# current-limiter.net
KiCad netlist of a schematic drawn in Altium Designer
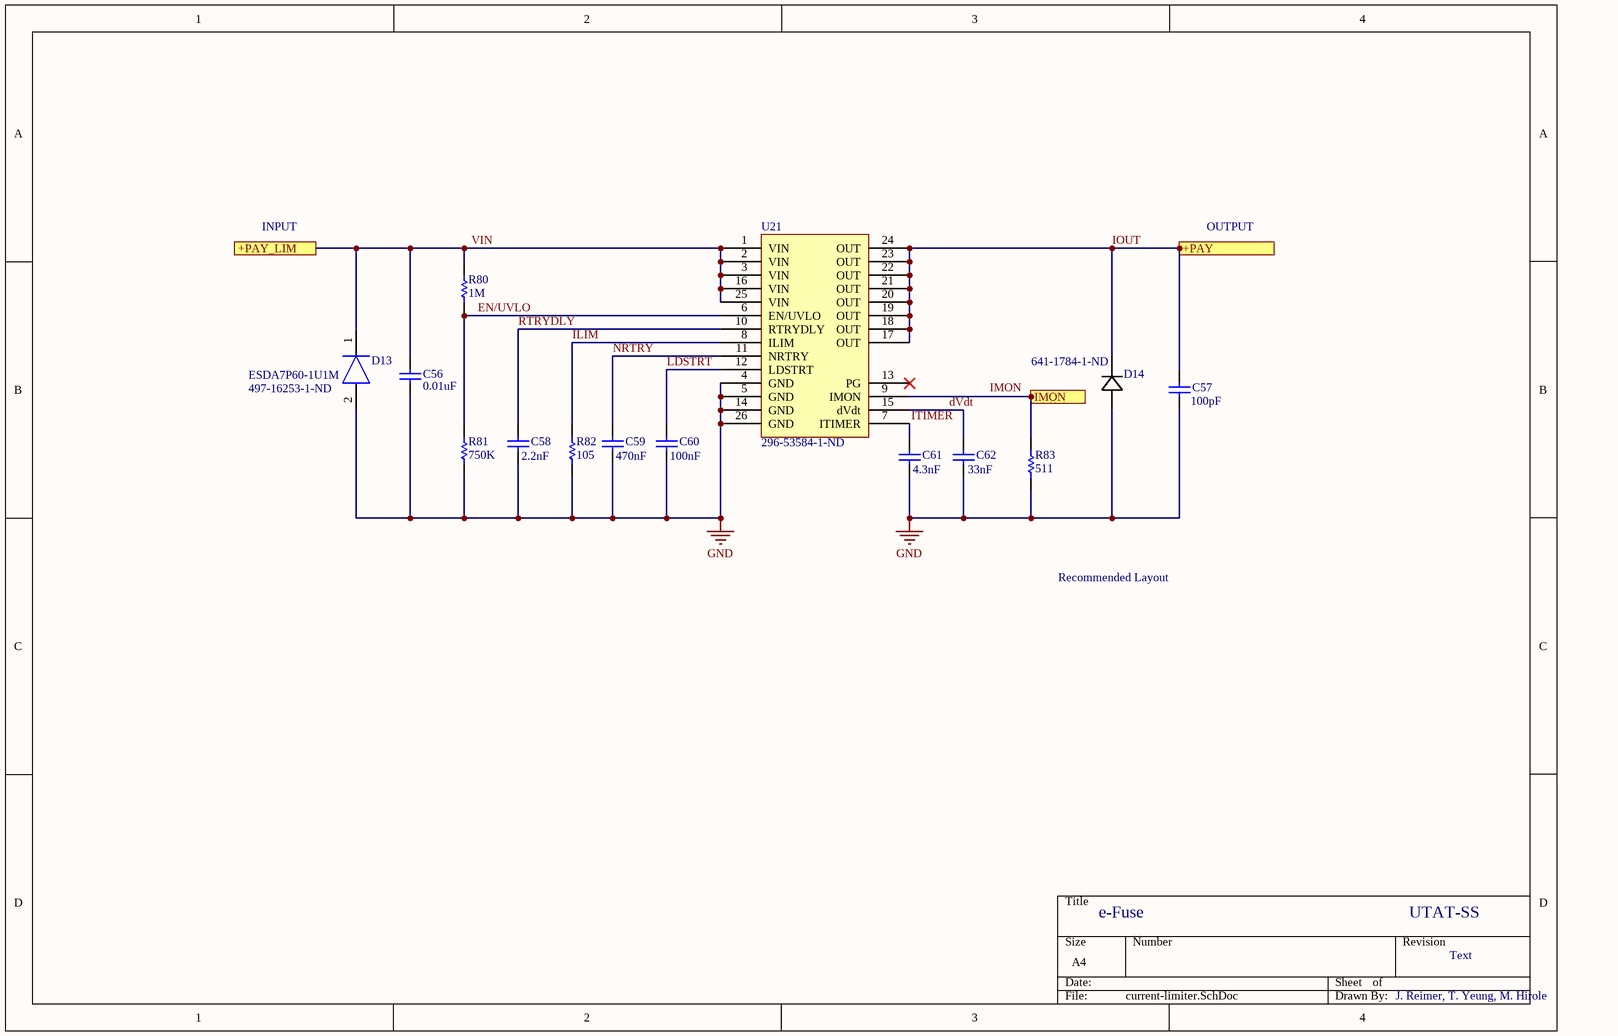
[diagram p0: current-limiter.SchDoc]

(export (version "E")
  (design (tool "Eeschema 10.0.6"))
  (components
    (comp (ref "C56")
      (value "0.01uF")
      (footprint "CAP0603R")
      (description "0603 capacitor")
      (fields (field (name "Comment") "0603"))
      (libsource (lib "heron-general") (part "CAP0603"))
    )
    (comp (ref "C57")
      (value "100pF")
      (footprint "CAP0603R")
      (description "0603 capacitor")
      (fields (field (name "Comment") "0603"))
      (libsource (lib "heron-general") (part "CAP0603"))
    )
    (comp (ref "C58")
      (value "2.2nF")
      (footprint "CAP0402R")
      (description "0402 capacitor")
      (fields (field (name "Comment") "0402"))
      (libsource (lib "heron-general") (part "CAP0402"))
    )
    (comp (ref "C59")
      (value "470nF")
      (footprint "CAP0402R")
      (description "0402 capacitor")
      (fields (field (name "Comment") "0402"))
      (libsource (lib "heron-general") (part "CAP0402"))
    )
    (comp (ref "C60")
      (value "100nF")
      (footprint "CAP0402R")
      (description "0402 capacitor")
      (fields (field (name "Comment") "0402"))
      (libsource (lib "heron-general") (part "CAP0402"))
    )
    (comp (ref "C61")
      (value "4.3nF")
      (footprint "CAP0402R")
      (description "0402 capacitor")
      (fields (field (name "Comment") "0402"))
      (libsource (lib "heron-general") (part "CAP0402"))
    )
    (comp (ref "C62")
      (value "33nF")
      (footprint "CAP0402R")
      (description "0402 capacitor")
      (fields (field (name "Comment") "0402"))
      (libsource (lib "heron-general") (part "CAP0402"))
    )
    (comp (ref "D13")
      (value "ESDA7P60-1U1M")
      (footprint "ESDA7P601U1M")
      (description "Diode")
      (fields
        (field (name "MOUSER PART NUMBER") "511-ESDA7P60-1U1M")
        (field (name "RS PART NUMBER") "1106381P")
        (field (name "SUPPLIER PART NUMBER 1") "497-16253-1-ND")
      )
      (libsource (lib "ESDA7P60-1U1M") (part "ESDA7P60-1U1M"))
    )
    (comp (ref "D14")
      (value "Part Number: 1SS389")
      (footprint "ESC")
      (description "No Description Available")
      (fields
        (field (name "MANUFACTURER_PART_NUMBER") "1SS389")
        (field (name "MANUFACTURER") "Comchip")
        (field (name "SUPPLIER PART NUMBER 1") "641-1784-1-ND")
        (field (name "COPYRIGHT") "Copyright (C) 2016 Accelerated Designs. All rights reserved")
      )
      (libsource (lib "1SS389") (part "1SS389"))
    )
    (comp (ref "R80")
      (value "1M")
      (footprint "RES0402R")
      (description "0402 resistor")
      (fields (field (name "Comment") "0402"))
      (libsource (lib "heron-general") (part "RES0402"))
    )
    (comp (ref "R81")
      (value "750K")
      (footprint "RES0402R")
      (description "0402 resistor")
      (fields (field (name "Comment") "0402"))
      (libsource (lib "heron-general") (part "RES0402"))
    )
    (comp (ref "R82")
      (value "105")
      (footprint "RES0402R")
      (description "0402 resistor")
      (fields (field (name "Comment") "0402"))
      (libsource (lib "heron-general") (part "RES0402"))
    )
    (comp (ref "R83")
      (value "511")
      (footprint "RES0402R")
      (description "0402 resistor")
      (fields (field (name "Comment") "0402"))
      (libsource (lib "heron-general") (part "RES0402"))
    )
    (comp (ref "U21")
      (value "eFuse")
      (footprint "RGE0024M")
      (description "2.7 - 24 V input supply, 15 A max load current")
      (fields
        (field (name "MANUFACTURER") "Texas Instruments")
        (field (name "MANUFACTURER PART NUMBER") "TPS259822LNRGER")
        (field (name "SUPPLIER PART NUMBER 1") "296-53584-1-ND")
      )
      (libsource (lib "heron-general") (part "TPS25982"))
    )
  )
  (nets
    (net (code "1") (name "/EN{slash}UVLO") (class "Default")
      (node (ref "R80") (pin "1") (pinfunction "1_1") (pintype "passive"))
      (node (ref "R81") (pin "2") (pinfunction "2_2") (pintype "passive"))
      (node (ref "U21") (pin "6") (pinfunction "EN/UVLO_6") (pintype "passive"))
    )
    (net (code "2") (name "/ILIM") (class "Default")
      (node (ref "R82") (pin "2") (pinfunction "2_2") (pintype "passive"))
      (node (ref "U21") (pin "8") (pinfunction "ILIM_8") (pintype "passive"))
    )
    (net (code "3") (name "/IMON") (class "Default")
      (node (ref "R83") (pin "2") (pinfunction "2_2") (pintype "passive"))
      (node (ref "U21") (pin "9") (pinfunction "IMON_9") (pintype "passive"))
    )
    (net (code "4") (name "/IOUT") (class "Default")
      (node (ref "C57") (pin "2") (pinfunction "2_2") (pintype "passive"))
      (node (ref "D14") (pin "1") (pinfunction "CATHODE_1") (pintype "passive"))
      (node (ref "U21") (pin "17") (pinfunction "OUT_17") (pintype "power_in"))
      (node (ref "U21") (pin "18") (pinfunction "OUT_18") (pintype "power_in"))
      (node (ref "U21") (pin "19") (pinfunction "OUT_19") (pintype "power_in"))
      (node (ref "U21") (pin "20") (pinfunction "OUT_20") (pintype "power_in"))
      (node (ref "U21") (pin "21") (pinfunction "OUT_21") (pintype "power_in"))
      (node (ref "U21") (pin "22") (pinfunction "OUT_22") (pintype "power_in"))
      (node (ref "U21") (pin "23") (pinfunction "OUT_23") (pintype "power_in"))
      (node (ref "U21") (pin "24") (pinfunction "OUT_24") (pintype "power_in"))
    )
    (net (code "6") (name "/LDSTRT") (class "Default")
      (node (ref "C60") (pin "2") (pinfunction "2_2") (pintype "passive"))
      (node (ref "U21") (pin "12") (pinfunction "LDSTRT_12") (pintype "passive"))
    )
    (net (code "7") (name "/NRTRY") (class "Default")
      (node (ref "C59") (pin "2") (pinfunction "2_2") (pintype "passive"))
      (node (ref "U21") (pin "11") (pinfunction "NRTRY_11") (pintype "passive"))
    )
    (net (code "8") (name "/RTRYDLY") (class "Default")
      (node (ref "C58") (pin "2") (pinfunction "2_2") (pintype "passive"))
      (node (ref "U21") (pin "10") (pinfunction "RTRYDLY_10") (pintype "passive"))
    )
    (net (code "9") (name "/VIN") (class "Default")
      (node (ref "C56") (pin "2") (pinfunction "2_2") (pintype "passive"))
      (node (ref "D13") (pin "1") (pinfunction "K_1") (pintype "passive"))
      (node (ref "R80") (pin "2") (pinfunction "2_2") (pintype "passive"))
      (node (ref "U21") (pin "1") (pinfunction "VIN_1") (pintype "power_in"))
      (node (ref "U21") (pin "16") (pinfunction "VIN_16") (pintype "power_in"))
      (node (ref "U21") (pin "2") (pinfunction "VIN_2") (pintype "power_in"))
      (node (ref "U21") (pin "25") (pinfunction "VIN_25") (pintype "power_in"))
      (node (ref "U21") (pin "3") (pinfunction "VIN_3") (pintype "power_in"))
    )
    (net (code "10") (name "/dVdt") (class "Default")
      (node (ref "C62") (pin "2") (pinfunction "2_2") (pintype "passive"))
      (node (ref "U21") (pin "15") (pinfunction "dVdt_15") (pintype "passive"))
    )
    (net (code "11") (name "GND") (class "Default")
      (node (ref "C56") (pin "1") (pinfunction "1_1") (pintype "passive"))
      (node (ref "C57") (pin "1") (pinfunction "1_1") (pintype "passive"))
      (node (ref "C58") (pin "1") (pinfunction "1_1") (pintype "passive"))
      (node (ref "C59") (pin "1") (pinfunction "1_1") (pintype "passive"))
      (node (ref "C60") (pin "1") (pinfunction "1_1") (pintype "passive"))
      (node (ref "C61") (pin "1") (pinfunction "1_1") (pintype "passive"))
      (node (ref "C62") (pin "1") (pinfunction "1_1") (pintype "passive"))
      (node (ref "D13") (pin "2") (pinfunction "A_2") (pintype "passive"))
      (node (ref "D14") (pin "2") (pinfunction "ANODE_2") (pintype "passive"))
      (node (ref "R81") (pin "1") (pinfunction "1_1") (pintype "passive"))
      (node (ref "R82") (pin "1") (pinfunction "1_1") (pintype "passive"))
      (node (ref "R83") (pin "1") (pinfunction "1_1") (pintype "passive"))
      (node (ref "U21") (pin "14") (pinfunction "GND_14") (pintype "power_in"))
      (node (ref "U21") (pin "26") (pinfunction "GND_26") (pintype "power_in"))
      (node (ref "U21") (pin "4") (pinfunction "GND_4") (pintype "power_in"))
      (node (ref "U21") (pin "5") (pinfunction "GND_5") (pintype "power_in"))
    )
    (net (code "12") (name "Net-(U21-ITIMER)") (class "Default")
      (node (ref "C61") (pin "2") (pinfunction "2_2") (pintype "passive"))
      (node (ref "U21") (pin "7") (pinfunction "ITIMER_7") (pintype "passive"))
    )
    (net (code "13") (name "unconnected-(U21-PG-Pad13)") (class "Default")
      (node (ref "U21") (pin "13") (pinfunction "PG_13") (pintype "passive+no_connect"))
    )
  )
)
